# TPDH-Walrus_v2_NoConn.net
KiCad netlist of a schematic drawn in EAGLE
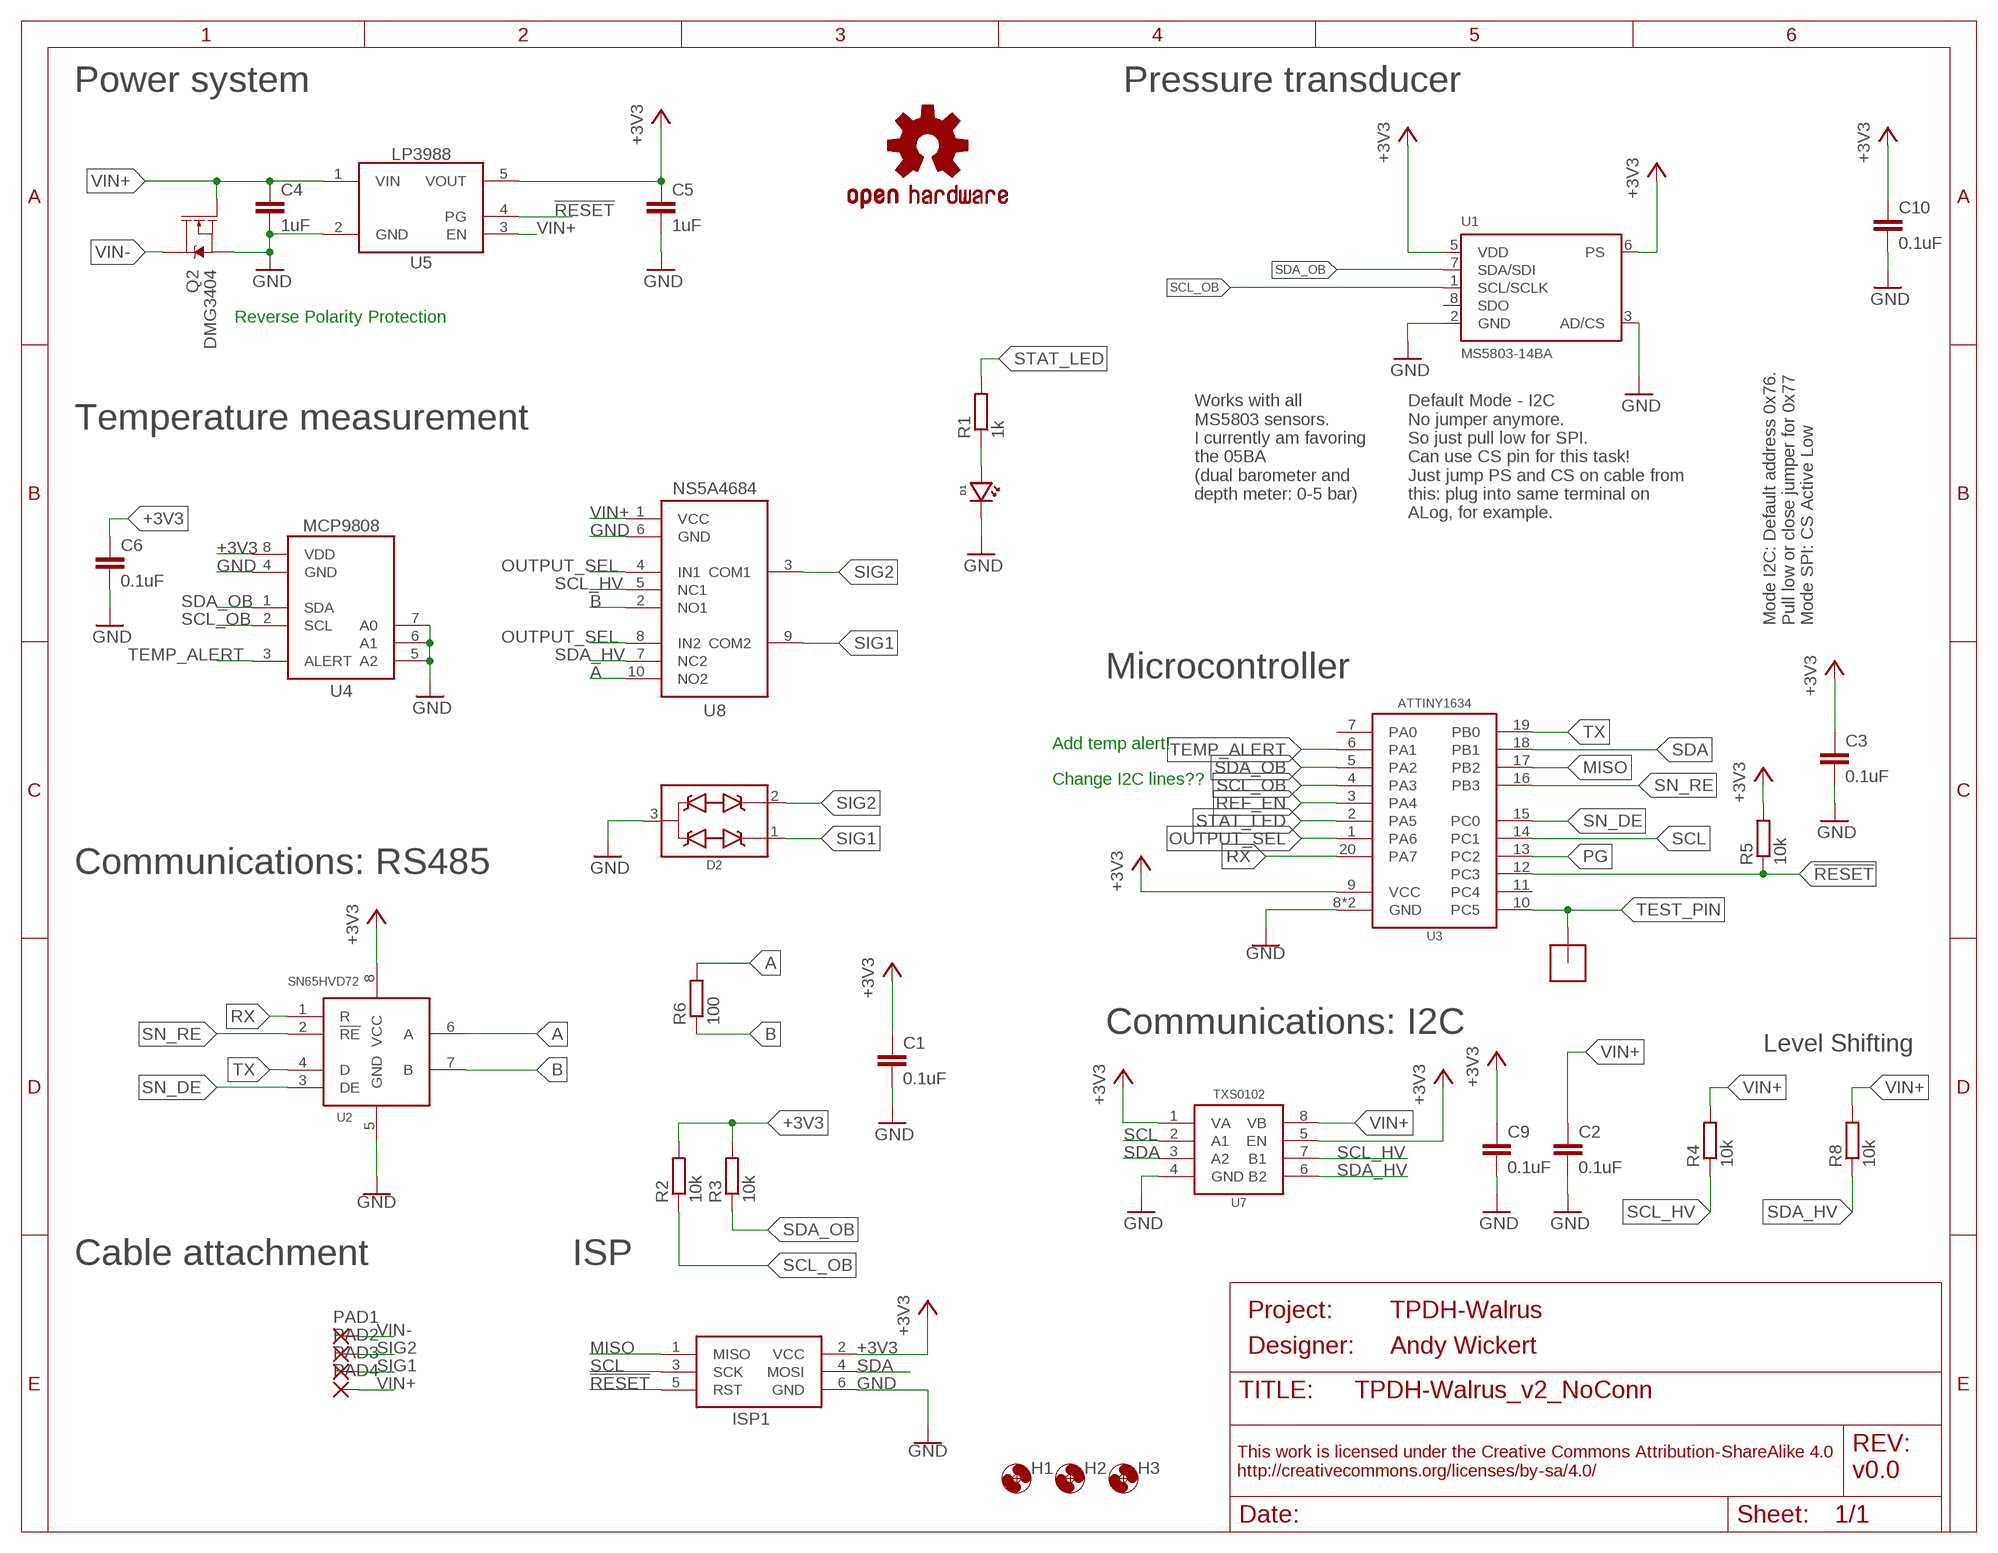
[diagram p0: schematic, sheet 1]

(export (version "E")
  (design (tool "Eeschema 10.0.6"))
  (components
    (comp (ref "C1")
      (value "0.1uF")
      (footprint "eagle-import:C0402")
      (fields (field (name "MF") "Murata") (field (name "MPN") "GCM155R71C104KA55D"))
      (libsource (lib "eagle-import") (part "C-EUC04020.1UF"))
    )
    (comp (ref "C2")
      (value "0.1uF")
      (footprint "eagle-import:C0402")
      (fields (field (name "MF") "Murata") (field (name "MPN") "GCM155R71C104KA55D"))
      (libsource (lib "eagle-import") (part "C-EUC04020.1UF"))
    )
    (comp (ref "C3")
      (value "0.1uF")
      (footprint "eagle-import:C0402")
      (fields (field (name "MF") "Murata") (field (name "MPN") "GCM155R71C104KA55D"))
      (libsource (lib "eagle-import") (part "C-EUC04020.1UF"))
    )
    (comp (ref "C4")
      (value "1uF")
      (footprint "eagle-import:C0603")
      (fields (field (name "MF") "Samsung") (field (name "MPN") "1276-6524-1-ND"))
      (libsource (lib "eagle-import") (part "C-EUC06031UF"))
    )
    (comp (ref "C5")
      (value "1uF")
      (footprint "eagle-import:C0603")
      (fields (field (name "MF") "Samsung") (field (name "MPN") "1276-6524-1-ND"))
      (libsource (lib "eagle-import") (part "C-EUC06031UF"))
    )
    (comp (ref "C6")
      (value "0.1uF")
      (footprint "eagle-import:C0402")
      (fields (field (name "MF") "Murata") (field (name "MPN") "GCM155R71C104KA55D"))
      (libsource (lib "eagle-import") (part "C-EUC04020.1UF"))
    )
    (comp (ref "C9")
      (value "0.1uF")
      (footprint "eagle-import:C0402")
      (fields (field (name "MF") "Murata") (field (name "MPN") "GCM155R71C104KA55D"))
      (libsource (lib "eagle-import") (part "C-EUC04020.1UF"))
    )
    (comp (ref "C10")
      (value "0.1uF")
      (footprint "eagle-import:C0402")
      (fields (field (name "MF") "Murata") (field (name "MPN") "GCM155R71C104KA55D"))
      (libsource (lib "eagle-import") (part "C-EUC04020.1UF"))
    )
    (comp (ref "D1")
      (value "LEDBLUE0603")
      (footprint "eagle-import:LED_0603")
      (fields (field (name "MF") "Wurth") (field (name "MPN") "150060BS75000"))
      (libsource (lib "eagle-import") (part "LED0603BLUE"))
    )
    (comp (ref "D2")
      (value "TVSSM712")
      (footprint "eagle-import:SOT23-3")
      (fields (field (name "MF") "Bourns") (field (name "MPN") "CDSOT23-SM712"))
      (libsource (lib "eagle-import") (part "TVSSM712"))
    )
    (comp (ref "H1")
      (value "MOUNTING_HOLE2_NP")
      (footprint "eagle-import:2_56")
      (libsource (lib "eagle-import") (part "MOUNTING_HOLE2_NP"))
    )
    (comp (ref "H2")
      (value "MOUNTING_HOLE2_NP")
      (footprint "eagle-import:2_56")
      (libsource (lib "eagle-import") (part "MOUNTING_HOLE2_NP"))
    )
    (comp (ref "H3")
      (value "MOUNTING_HOLE2_NP")
      (footprint "eagle-import:2_56")
      (libsource (lib "eagle-import") (part "MOUNTING_HOLE2_NP"))
    )
    (comp (ref "ISP1")
      (value "AVRISP-6")
      (footprint "eagle-import:AVRISP")
      (libsource (lib "eagle-import") (part "AVRISP-6"))
    )
    (comp (ref "LOGO1")
      (value "OSHW-LOGOM")
      (footprint "eagle-import:OSHW-LOGO-M")
      (libsource (lib "eagle-import") (part "OSHW-LOGOM"))
    )
    (comp (ref "PAD1")
      (value "PAD1.1MM")
      (footprint "eagle-import:2,54_1,1")
      (libsource (lib "eagle-import") (part "PAD1.1MM"))
    )
    (comp (ref "PAD2")
      (value "PAD1.1MM")
      (footprint "eagle-import:2,54_1,1")
      (libsource (lib "eagle-import") (part "PAD1.1MM"))
    )
    (comp (ref "PAD3")
      (value "PAD1.1MM")
      (footprint "eagle-import:2,54_1,1")
      (libsource (lib "eagle-import") (part "PAD1.1MM"))
    )
    (comp (ref "PAD4")
      (value "PAD1.1MM")
      (footprint "eagle-import:2,54_1,1")
      (libsource (lib "eagle-import") (part "PAD1.1MM"))
    )
    (comp (ref "Q2")
      (value "DMG3404")
      (footprint "eagle-import:SOT23-3")
      (fields (field (name "MF") "Diodes Incorporated") (field (name "MPN") "DMG3404L-7"))
      (libsource (lib "eagle-import") (part "MOSFET-NCH-DMG3404L"))
    )
    (comp (ref "R1")
      (value "1k")
      (footprint "eagle-import:R0603")
      (fields (field (name "MF") "Yageo") (field (name "MPN") "AC0603FR-071KL"))
      (libsource (lib "eagle-import") (part "R-EU_R06031K"))
    )
    (comp (ref "R2")
      (value "10k")
      (footprint "eagle-import:R0402")
      (fields (field (name "MF") "Yageo") (field (name "MPN") "RC0402FR-0710KL"))
      (libsource (lib "eagle-import") (part "R-EU_R040210K"))
    )
    (comp (ref "R3")
      (value "10k")
      (footprint "eagle-import:R0402")
      (fields (field (name "MF") "Yageo") (field (name "MPN") "RC0402FR-0710KL"))
      (libsource (lib "eagle-import") (part "R-EU_R040210K"))
    )
    (comp (ref "R4")
      (value "10k")
      (footprint "eagle-import:R0402")
      (fields (field (name "MF") "Yageo") (field (name "MPN") "RC0402FR-0710KL"))
      (libsource (lib "eagle-import") (part "R-EU_R040210K"))
    )
    (comp (ref "R5")
      (value "10k")
      (footprint "eagle-import:R0402")
      (fields (field (name "MF") "Yageo") (field (name "MPN") "RC0402FR-0710KL"))
      (libsource (lib "eagle-import") (part "R-EU_R040210K"))
    )
    (comp (ref "R6")
      (value "100")
      (footprint "eagle-import:R0402")
      (fields (field (name "MF") "Yageo") (field (name "MPN") "RC0402FR-07100RL"))
      (libsource (lib "eagle-import") (part "R-EU_R0402100"))
    )
    (comp (ref "R8")
      (value "10k")
      (footprint "eagle-import:R0402")
      (fields (field (name "MF") "Yageo") (field (name "MPN") "RC0402FR-0710KL"))
      (libsource (lib "eagle-import") (part "R-EU_R040210K"))
    )
    (comp (ref "U$12")
      (value "POGO_PAD")
      (footprint "eagle-import:POGO_PAD")
      (libsource (lib "eagle-import") (part "POGO_PAD"))
    )
    (comp (ref "U1")
      (value "MS5803-14BA")
      (footprint "eagle-import:MS5803")
      (fields (field (name "MF") "TE") (field (name "MPN") "MS580305BA01-00"))
      (libsource (lib "eagle-import") (part "MS5803-14BA"))
    )
    (comp (ref "U2")
      (value "SN65HVD72DSOIC")
      (footprint "eagle-import:SO08")
      (fields (field (name "DISP") "SN65HVD72") (field (name "MF") "TI") (field (name "MPN") "SN65HVD72DR"))
      (libsource (lib "eagle-import") (part "SN65HVD72SOICD"))
    )
    (comp (ref "U3")
      (value "ATTINY1634QFN")
      (footprint "eagle-import:QFN20")
      (fields (field (name "MF") "Atmel") (field (name "MPN") "ATTINY1634-MUR"))
      (libsource (lib "eagle-import") (part "ATTINY1634QFN"))
    )
    (comp (ref "U4")
      (value "MCP9808MSOP")
      (footprint "eagle-import:MSOP_8")
      (fields (field (name "MF") "Microchip") (field (name "MPN") "MCP9808T-E/MS"))
      (libsource (lib "eagle-import") (part "MCP9808MSOP"))
    )
    (comp (ref "U5")
      (value "LP39883.3VDBV")
      (footprint "eagle-import:DBV0005A")
      (fields (field (name "MF") "TI") (field (name "MPN") "LP3988IMF-3.3/NOPB"))
      (libsource (lib "eagle-import") (part "LP3988DBV3.3V"))
    )
    (comp (ref "U7")
      (value "TXS0102DQM")
      (footprint "eagle-import:DQM_R-PX2SON-N8")
      (fields (field (name "MF") "TI") (field (name "MPN") "TXS0102DQMR"))
      (libsource (lib "eagle-import") (part "TXS0102DQM"))
    )
    (comp (ref "U8")
      (value "NS5A4684S")
      (footprint "eagle-import:WQFN10")
      (fields
        (field (name "DISP") "NS5A4684")
        (field (name "MF") "ON Semiconductor")
        (field (name "MPN") "NS5A4684SMNTAG")
      )
      (libsource (lib "eagle-import") (part "NS5A4684S"))
    )
  )
  (nets
    (net (code "1") (name "+3V3") (class "Default")
      (node (ref "C1") (pin "1") (pinfunction "1_1") (pintype "passive"))
      (node (ref "C10") (pin "1") (pinfunction "1_1") (pintype "passive"))
      (node (ref "C3") (pin "1") (pinfunction "1_1") (pintype "passive"))
      (node (ref "C5") (pin "1") (pinfunction "1_1") (pintype "passive"))
      (node (ref "C6") (pin "1") (pinfunction "1_1") (pintype "passive"))
      (node (ref "C9") (pin "1") (pinfunction "1_1") (pintype "passive"))
      (node (ref "ISP1") (pin "2") (pinfunction "VCC_2") (pintype "power_in"))
      (node (ref "R2") (pin "2") (pinfunction "2_2") (pintype "passive"))
      (node (ref "R3") (pin "2") (pinfunction "2_2") (pintype "passive"))
      (node (ref "R5") (pin "2") (pinfunction "2_2") (pintype "passive"))
      (node (ref "U1") (pin "5") (pinfunction "VDD_5") (pintype "bidirectional"))
      (node (ref "U1") (pin "6") (pinfunction "PS_6") (pintype "bidirectional"))
      (node (ref "U2") (pin "8") (pinfunction "VCC_8") (pintype "power_in"))
      (node (ref "U3") (pin "9") (pinfunction "VCC_9") (pintype "power_in"))
      (node (ref "U4") (pin "8") (pinfunction "VDD_8") (pintype "power_in"))
      (node (ref "U5") (pin "5") (pinfunction "VOUT_5") (pintype "power_in"))
      (node (ref "U7") (pin "1") (pinfunction "VA_1") (pintype "power_in"))
      (node (ref "U7") (pin "5") (pinfunction "EN_5") (pintype "input"))
    )
    (net (code "2") (name "/~{RESET}") (class "Default")
      (node (ref "ISP1") (pin "5") (pinfunction "RST_5") (pintype "output"))
      (node (ref "R5") (pin "1") (pinfunction "1_1") (pintype "passive"))
      (node (ref "U3") (pin "12") (pinfunction "PC3_12") (pintype "bidirectional"))
      (node (ref "U5") (pin "4") (pinfunction "PG_4") (pintype "output"))
    )
    (net (code "3") (name "A") (class "Default")
      (node (ref "R6") (pin "2") (pinfunction "2_2") (pintype "passive"))
      (node (ref "U2") (pin "6") (pinfunction "A_6") (pintype "bidirectional"))
      (node (ref "U8") (pin "10") (pinfunction "NO2_10") (pintype "bidirectional"))
    )
    (net (code "4") (name "B") (class "Default")
      (node (ref "R6") (pin "1") (pinfunction "1_1") (pintype "passive"))
      (node (ref "U2") (pin "7") (pinfunction "B_7") (pintype "bidirectional"))
      (node (ref "U8") (pin "2") (pinfunction "NO1_2") (pintype "bidirectional"))
    )
    (net (code "5") (name "GND") (class "Default")
      (node (ref "C1") (pin "2") (pinfunction "2_2") (pintype "passive"))
      (node (ref "C10") (pin "2") (pinfunction "2_2") (pintype "passive"))
      (node (ref "C2") (pin "2") (pinfunction "2_2") (pintype "passive"))
      (node (ref "C3") (pin "2") (pinfunction "2_2") (pintype "passive"))
      (node (ref "C4") (pin "2") (pinfunction "2_2") (pintype "passive"))
      (node (ref "C5") (pin "2") (pinfunction "2_2") (pintype "passive"))
      (node (ref "C6") (pin "2") (pinfunction "2_2") (pintype "passive"))
      (node (ref "C9") (pin "2") (pinfunction "2_2") (pintype "passive"))
      (node (ref "D1") (pin "CATHODE") (pinfunction "CATHODE_CATHODE") (pintype "power_in"))
      (node (ref "D2") (pin "3") (pinfunction "COM_3") (pintype "input"))
      (node (ref "ISP1") (pin "6") (pinfunction "GND_6") (pintype "power_in"))
      (node (ref "Q2") (pin "2") (pinfunction "S_2") (pintype "bidirectional"))
      (node (ref "U1") (pin "2") (pinfunction "GND_2") (pintype "bidirectional"))
      (node (ref "U1") (pin "3") (pinfunction "AD/CS_3") (pintype "bidirectional"))
      (node (ref "U2") (pin "5") (pinfunction "GND_5") (pintype "power_in"))
      (node (ref "U3") (pin "8") (pinfunction "GND_8") (pintype "power_in"))
      (node (ref "U3") (pin "EP") (pinfunction "GND_EP") (pintype "power_in"))
      (node (ref "U4") (pin "4") (pinfunction "GND_4") (pintype "power_in"))
      (node (ref "U4") (pin "5") (pinfunction "A2_5") (pintype "input"))
      (node (ref "U4") (pin "6") (pinfunction "A1_6") (pintype "input"))
      (node (ref "U4") (pin "7") (pinfunction "A0_7") (pintype "input"))
      (node (ref "U5") (pin "2") (pinfunction "GND_2") (pintype "power_in"))
      (node (ref "U7") (pin "4") (pinfunction "GND_4") (pintype "power_in"))
      (node (ref "U8") (pin "6") (pinfunction "GND_6") (pintype "power_in"))
    )
    (net (code "6") (name "MISO") (class "Default")
      (node (ref "ISP1") (pin "1") (pinfunction "MISO_1") (pintype "input"))
      (node (ref "U3") (pin "17") (pinfunction "PB2_17") (pintype "bidirectional"))
    )
    (net (code "7") (name "Net-(D1-PadANODE)") (class "Default")
      (node (ref "D1") (pin "ANODE") (pinfunction "ANODE_ANODE") (pintype "power_in"))
      (node (ref "R1") (pin "1") (pinfunction "1_1") (pintype "passive"))
    )
    (net (code "8") (name "OUTPUT_SEL") (class "Default")
      (node (ref "U3") (pin "1") (pinfunction "PA6_1") (pintype "bidirectional"))
      (node (ref "U8") (pin "4") (pinfunction "IN1_4") (pintype "input"))
      (node (ref "U8") (pin "8") (pinfunction "IN2_8") (pintype "input"))
    )
    (net (code "9") (name "PG") (class "Default")
      (node (ref "U3") (pin "13") (pinfunction "PC2_13") (pintype "bidirectional"))
    )
    (net (code "10") (name "REF_EN") (class "Default")
      (node (ref "U3") (pin "3") (pinfunction "PA4_3") (pintype "bidirectional"))
    )
    (net (code "11") (name "RX") (class "Default")
      (node (ref "U2") (pin "1") (pinfunction "R_1") (pintype "output"))
      (node (ref "U3") (pin "20") (pinfunction "PA7_20") (pintype "bidirectional"))
    )
    (net (code "12") (name "SCL") (class "Default")
      (node (ref "ISP1") (pin "3") (pinfunction "SCK_3") (pintype "output"))
      (node (ref "U3") (pin "14") (pinfunction "PC1_14") (pintype "bidirectional"))
      (node (ref "U7") (pin "2") (pinfunction "A1_2") (pintype "bidirectional"))
    )
    (net (code "13") (name "SCL_HV") (class "Default")
      (node (ref "R4") (pin "1") (pinfunction "1_1") (pintype "passive"))
      (node (ref "U7") (pin "7") (pinfunction "B1_7") (pintype "bidirectional"))
      (node (ref "U8") (pin "5") (pinfunction "NC1_5") (pintype "bidirectional"))
    )
    (net (code "14") (name "SCL_OB") (class "Default")
      (node (ref "R2") (pin "1") (pinfunction "1_1") (pintype "passive"))
      (node (ref "U1") (pin "1") (pinfunction "SCL/SCLK_1") (pintype "bidirectional"))
      (node (ref "U3") (pin "4") (pinfunction "PA3_4") (pintype "bidirectional"))
      (node (ref "U4") (pin "2") (pinfunction "SCL_2") (pintype "input"))
    )
    (net (code "15") (name "SDA") (class "Default")
      (node (ref "ISP1") (pin "4") (pinfunction "MOSI_4") (pintype "output"))
      (node (ref "U3") (pin "18") (pinfunction "PB1_18") (pintype "bidirectional"))
      (node (ref "U7") (pin "3") (pinfunction "A2_3") (pintype "bidirectional"))
    )
    (net (code "16") (name "SDA_HV") (class "Default")
      (node (ref "R8") (pin "1") (pinfunction "1_1") (pintype "passive"))
      (node (ref "U7") (pin "6") (pinfunction "B2_6") (pintype "bidirectional"))
      (node (ref "U8") (pin "7") (pinfunction "NC2_7") (pintype "bidirectional"))
    )
    (net (code "17") (name "SDA_OB") (class "Default")
      (node (ref "R3") (pin "1") (pinfunction "1_1") (pintype "passive"))
      (node (ref "U1") (pin "7") (pinfunction "SDA/SDI_7") (pintype "bidirectional"))
      (node (ref "U3") (pin "5") (pinfunction "PA2_5") (pintype "bidirectional"))
      (node (ref "U4") (pin "1") (pinfunction "SDA_1") (pintype "bidirectional"))
    )
    (net (code "18") (name "SIG1") (class "Default")
      (node (ref "D2") (pin "1") (pinfunction "D1_1") (pintype "input"))
      (node (ref "PAD3") (pin "1") (pinfunction "P_1") (pintype "passive"))
      (node (ref "U8") (pin "9") (pinfunction "COM2_9") (pintype "bidirectional"))
    )
    (net (code "19") (name "SIG2") (class "Default")
      (node (ref "D2") (pin "2") (pinfunction "D2_2") (pintype "input"))
      (node (ref "PAD2") (pin "1") (pinfunction "P_1") (pintype "passive"))
      (node (ref "U8") (pin "3") (pinfunction "COM1_3") (pintype "bidirectional"))
    )
    (net (code "20") (name "SN_DE") (class "Default")
      (node (ref "U2") (pin "3") (pinfunction "DE_3") (pintype "input"))
      (node (ref "U3") (pin "15") (pinfunction "PC0_15") (pintype "bidirectional"))
    )
    (net (code "21") (name "SN_RE") (class "Default")
      (node (ref "U2") (pin "2") (pinfunction "~{RE}_2") (pintype "input"))
      (node (ref "U3") (pin "16") (pinfunction "PB3_16") (pintype "bidirectional"))
    )
    (net (code "22") (name "STAT_LED") (class "Default")
      (node (ref "R1") (pin "2") (pinfunction "2_2") (pintype "passive"))
      (node (ref "U3") (pin "2") (pinfunction "PA5_2") (pintype "bidirectional"))
    )
    (net (code "23") (name "TEMP_ALERT") (class "Default")
      (node (ref "U3") (pin "6") (pinfunction "PA1_6") (pintype "bidirectional"))
      (node (ref "U4") (pin "3") (pinfunction "ALERT_3") (pintype "output"))
    )
    (net (code "24") (name "TEST_PIN") (class "Default")
      (node (ref "U$12") (pin "P$1") (pinfunction "P$1_P$1") (pintype "bidirectional"))
      (node (ref "U3") (pin "10") (pinfunction "PC5_10") (pintype "bidirectional"))
    )
    (net (code "25") (name "TX") (class "Default")
      (node (ref "U2") (pin "4") (pinfunction "D_4") (pintype "input"))
      (node (ref "U3") (pin "19") (pinfunction "PB0_19") (pintype "bidirectional"))
    )
    (net (code "26") (name "VIN+") (class "Default")
      (node (ref "C2") (pin "1") (pinfunction "1_1") (pintype "passive"))
      (node (ref "C4") (pin "1") (pinfunction "1_1") (pintype "passive"))
      (node (ref "PAD4") (pin "1") (pinfunction "P_1") (pintype "passive"))
      (node (ref "Q2") (pin "1") (pinfunction "G_1") (pintype "bidirectional"))
      (node (ref "R4") (pin "2") (pinfunction "2_2") (pintype "passive"))
      (node (ref "R8") (pin "2") (pinfunction "2_2") (pintype "passive"))
      (node (ref "U5") (pin "1") (pinfunction "VIN_1") (pintype "power_in"))
      (node (ref "U5") (pin "3") (pinfunction "EN_3") (pintype "input"))
      (node (ref "U7") (pin "8") (pinfunction "VB_8") (pintype "power_in"))
      (node (ref "U8") (pin "1") (pinfunction "VCC_1") (pintype "power_in"))
    )
    (net (code "27") (name "VIN-") (class "Default")
      (node (ref "PAD1") (pin "1") (pinfunction "P_1") (pintype "passive"))
      (node (ref "Q2") (pin "3") (pinfunction "D_3") (pintype "bidirectional"))
    )
    (net (code "28") (name "unconnected-(U1-SDO-Pad8)") (class "Default")
      (node (ref "U1") (pin "8") (pinfunction "SDO_8") (pintype "bidirectional"))
    )
    (net (code "29") (name "unconnected-(U3-PA0-Pad7)") (class "Default")
      (node (ref "U3") (pin "7") (pinfunction "PA0_7") (pintype "bidirectional"))
    )
    (net (code "30") (name "unconnected-(U3-PC4-Pad11)") (class "Default")
      (node (ref "U3") (pin "11") (pinfunction "PC4_11") (pintype "bidirectional"))
    )
  )
)
